# ADC.net
KiCad netlist of a schematic drawn in Altium Designer
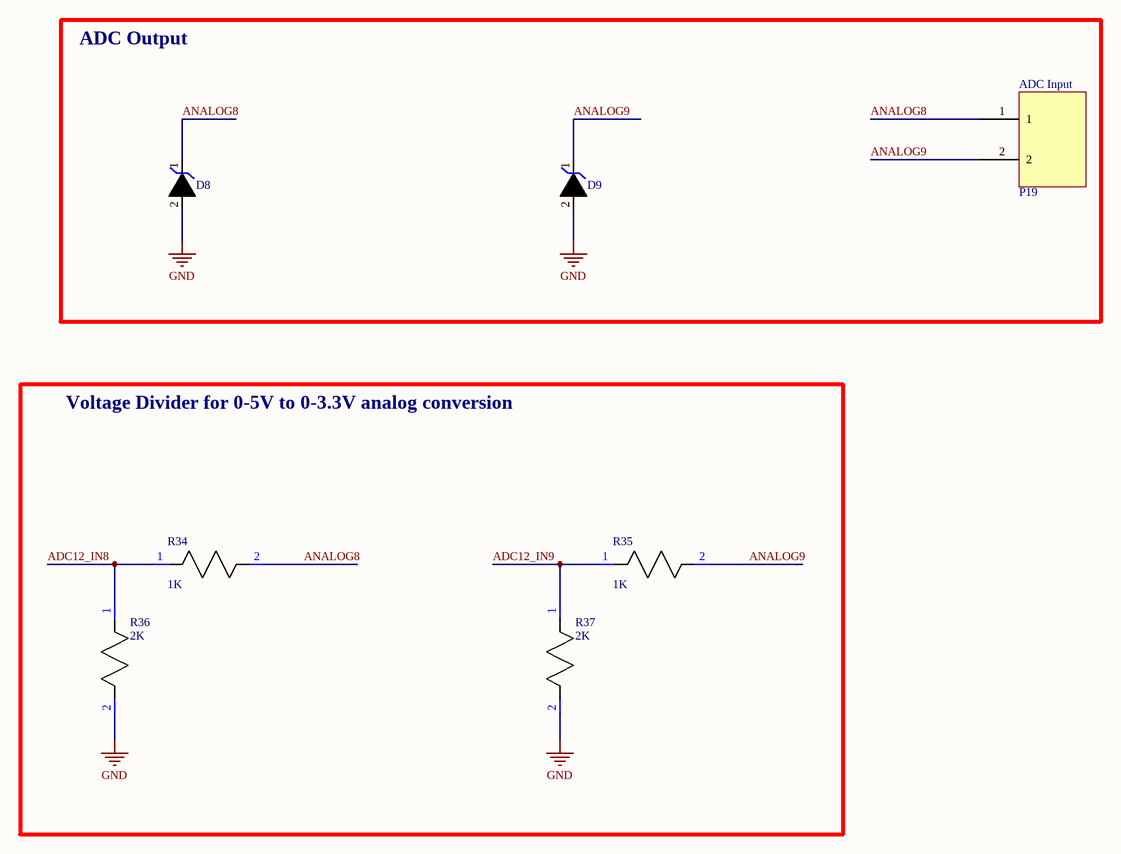
[diagram p0: ADC.SchDoc]

(export (version "E")
  (design (tool "Eeschema 10.0.6"))
  (components
    (comp (ref "D8")
      (value "TVS")
      (footprint "TVS DIODE")
      (description "Schematic for TVS diode")
      (libsource (lib "Lib") (part "TVS Diode"))
    )
    (comp (ref "D9")
      (value "TVS")
      (footprint "TVS DIODE")
      (description "Schematic for TVS diode")
      (libsource (lib "Lib") (part "TVS Diode"))
    )
    (comp (ref "P19")
      (value "ADC Input")
      (footprint "WR-TBL 322 2H")
      (description "322 series 2 pin header")
      (libsource (lib "Lib") (part "322-2H"))
    )
    (comp (ref "R34")
      (value "1K")
      (footprint "0603 RES")
      (description "Can be used for SMD resistors")
      (fields (field (name "Comment") "Resistor"))
      (libsource (lib "Lib") (part "0603 Res"))
    )
    (comp (ref "R35")
      (value "1K")
      (footprint "0603 RES")
      (description "Can be used for SMD resistors")
      (fields (field (name "Comment") "Resistor"))
      (libsource (lib "Lib") (part "0603 Res"))
    )
    (comp (ref "R36")
      (value "2K")
      (footprint "0603 RES")
      (description "Can be used for SMD resistors")
      (fields (field (name "Comment") "Resistor"))
      (libsource (lib "Lib") (part "0603 Res"))
    )
    (comp (ref "R37")
      (value "2K")
      (footprint "0603 RES")
      (description "Can be used for SMD resistors")
      (fields (field (name "Comment") "Resistor"))
      (libsource (lib "Lib") (part "0603 Res"))
    )
  )
  (nets
    (net (code "1") (name "/ADC12_IN8") (class "Default")
      (node (ref "R34") (pin "1") (pinfunction "22_1") (pintype "passive"))
      (node (ref "R36") (pin "1") (pinfunction "22_1") (pintype "passive"))
    )
    (net (code "2") (name "/ADC12_IN9") (class "Default")
      (node (ref "R35") (pin "1") (pinfunction "22_1") (pintype "passive"))
      (node (ref "R37") (pin "1") (pinfunction "22_1") (pintype "passive"))
    )
    (net (code "3") (name "/ANALOG8") (class "Default")
      (node (ref "D8") (pin "1") (pinfunction "1_1") (pintype "passive"))
      (node (ref "P19") (pin "1") (pinfunction "1_1") (pintype "passive"))
      (node (ref "R34") (pin "2") (pinfunction "21_2") (pintype "passive"))
    )
    (net (code "4") (name "/ANALOG9") (class "Default")
      (node (ref "D9") (pin "1") (pinfunction "1_1") (pintype "passive"))
      (node (ref "P19") (pin "2") (pinfunction "2_2") (pintype "passive"))
      (node (ref "R35") (pin "2") (pinfunction "21_2") (pintype "passive"))
    )
    (net (code "5") (name "GND") (class "Default")
      (node (ref "D8") (pin "2") (pinfunction "2_2") (pintype "passive"))
      (node (ref "D9") (pin "2") (pinfunction "2_2") (pintype "passive"))
      (node (ref "R36") (pin "2") (pinfunction "21_2") (pintype "passive"))
      (node (ref "R37") (pin "2") (pinfunction "21_2") (pintype "passive"))
    )
  )
)
